# MCU_nRF5340.net
KiCad netlist of a schematic drawn in Altium Designer
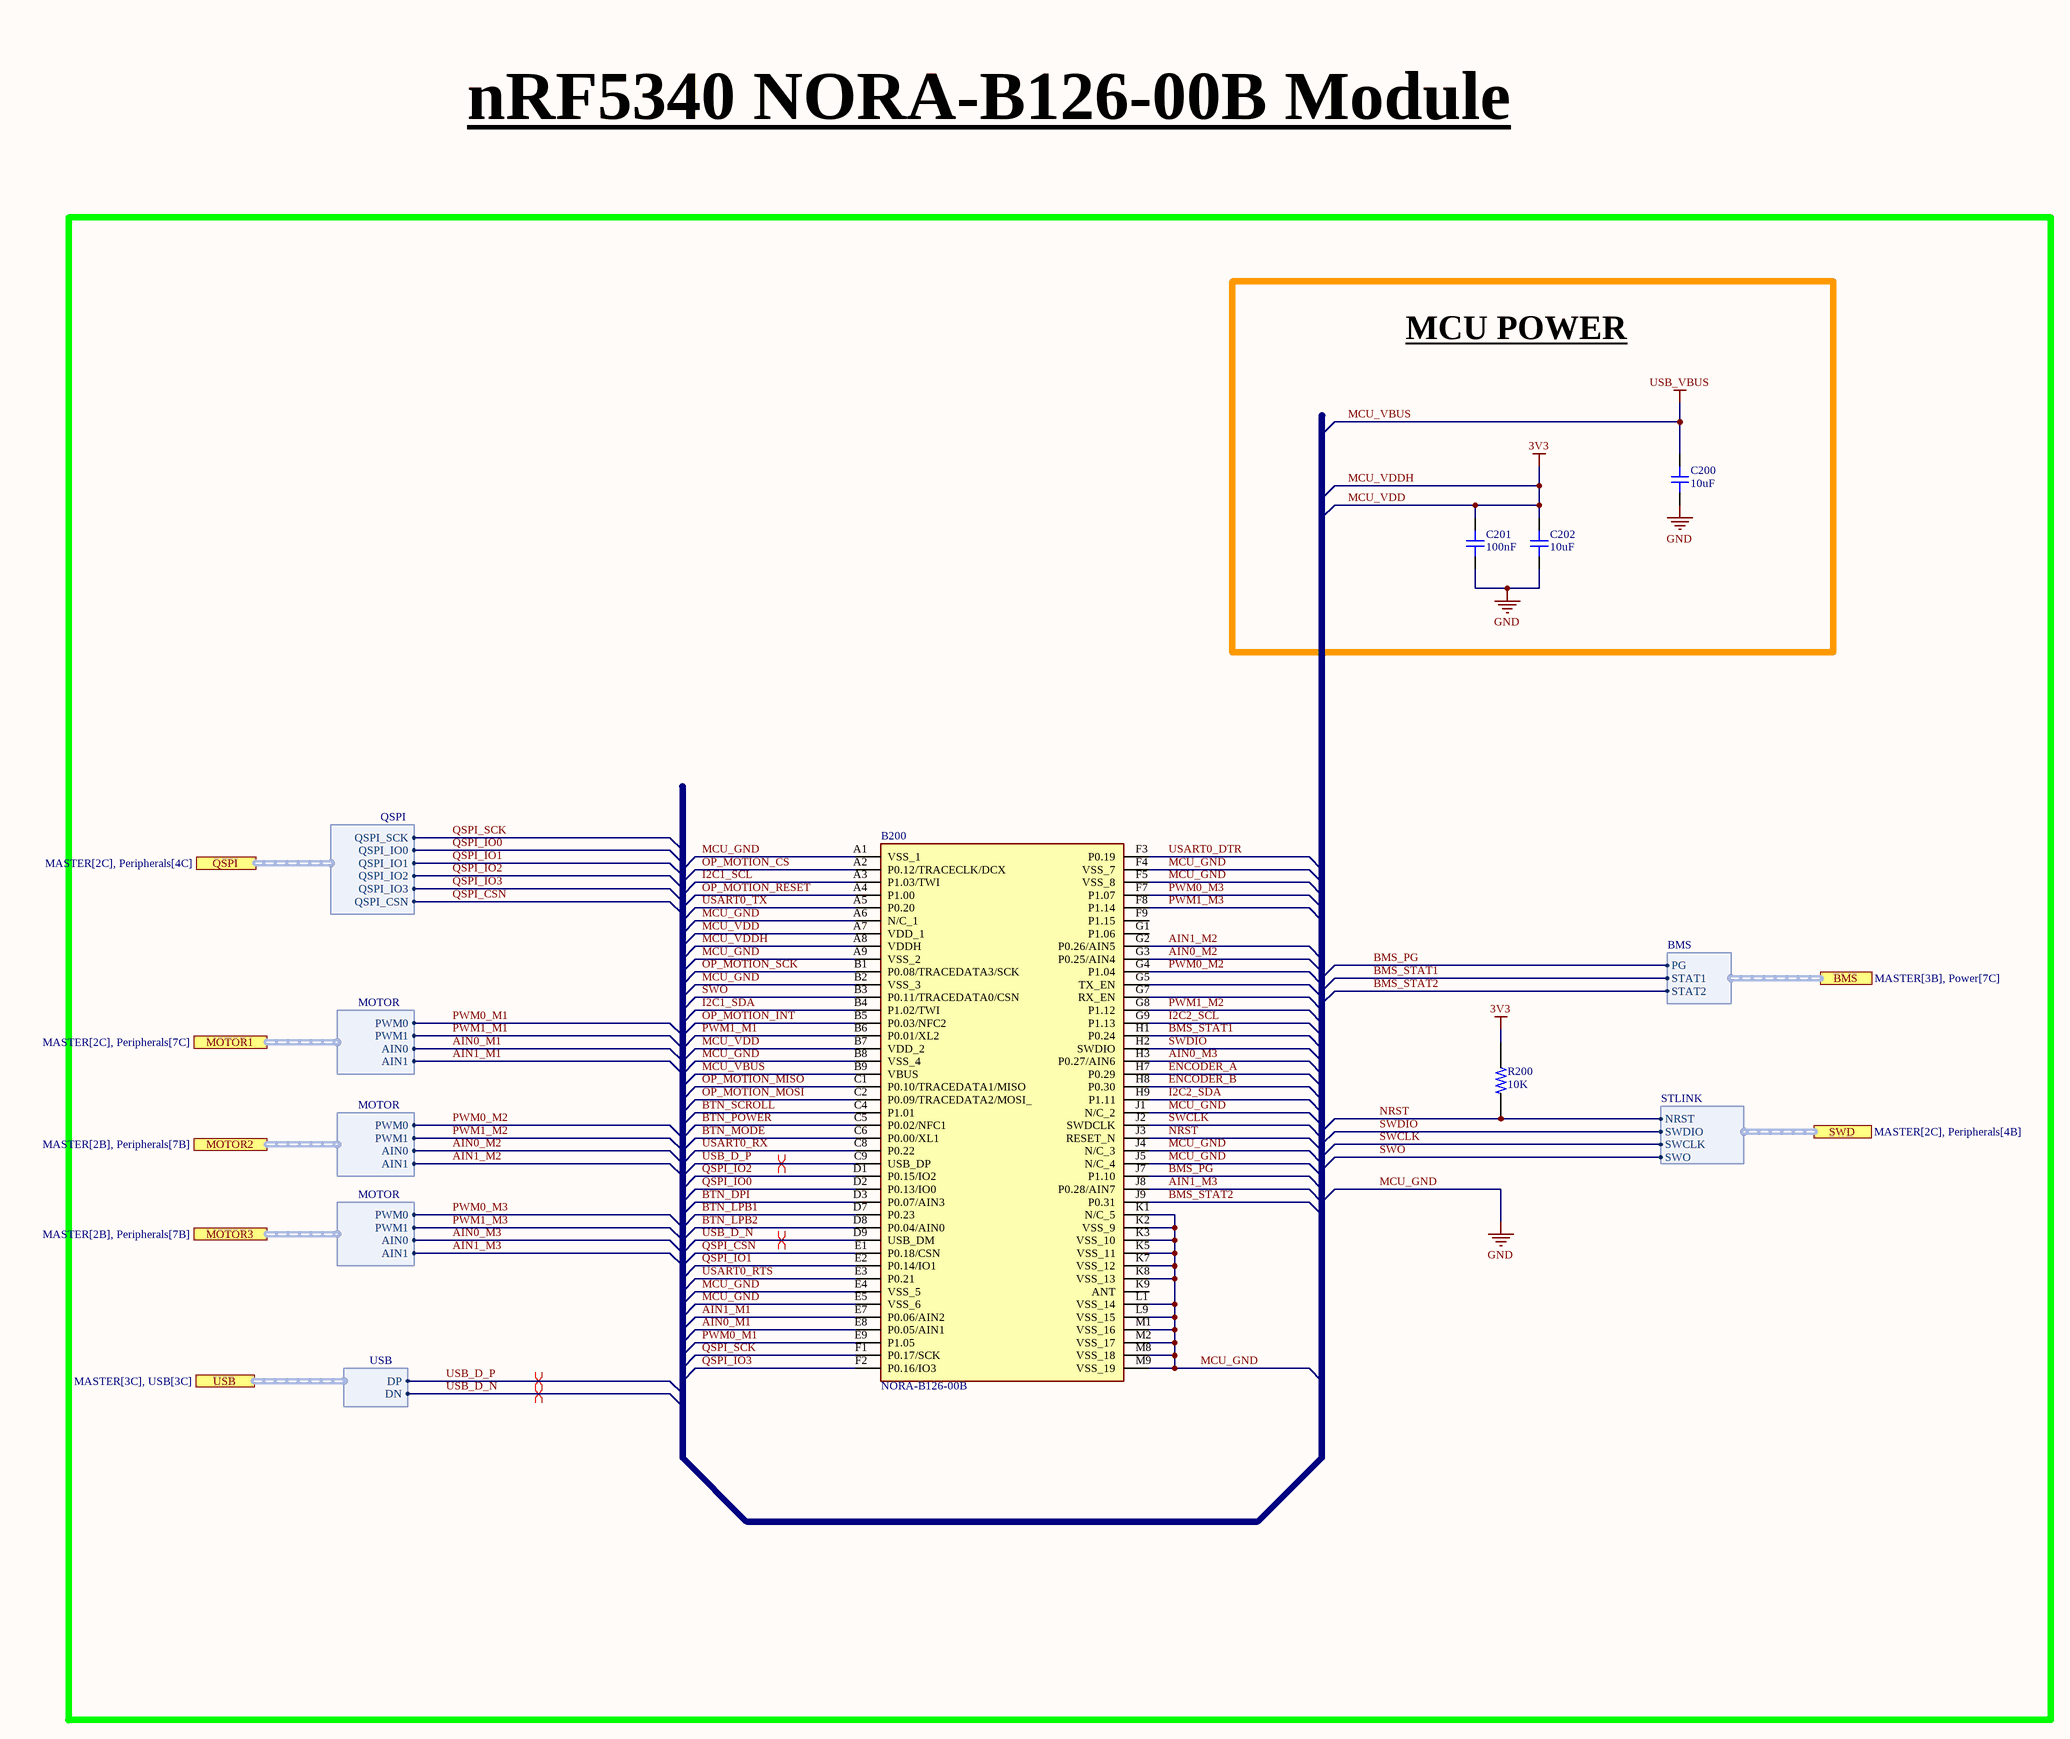
[diagram p0: MCU_nRF5340.SchDoc]

(export (version "E")
  (design (tool "Eeschema 10.0.6"))
  (components
    (comp (ref "B200")
      (value "NORA-B126-00B")
      (footprint "NORAB12600B")
      (description "Stand-alone dual-core Bluetooth 5.2 Low Energy and IEEE 802.15.4 module")
      (fields (field (name "MOUSER PART NUMBER") "377-NORA-B126-00B"))
      (libsource (lib "board") (part "NORA-B126-00B"))
    )
    (comp (ref "C200")
      (value "10uF")
      (footprint "CAP_0603")
      (description "Capacitor SMD 0603")
      (libsource (lib "board") (part "CAP_0603"))
    )
    (comp (ref "C201")
      (value "100nF")
      (footprint "CAP_0603")
      (description "Capacitor SMD 0603")
      (libsource (lib "board") (part "CAP_0603"))
    )
    (comp (ref "C202")
      (value "10uF")
      (footprint "CAP_0603")
      (description "Capacitor SMD 0603")
      (libsource (lib "board") (part "CAP_0603"))
    )
    (comp (ref "R200")
      (value "10K")
      (footprint "RESC1607X60N")
      (description "10 kOhms Â±5% 0.1W, 1/10W Chip Resistor 0603 (1608 Metric) Moisture Resistant Thick Film")
      (fields (field (name "MF") "Yageo") (field (name "MP") "RC0603JR0710KL"))
      (libsource (lib "board") (part "RC0603JR0710KL"))
    )
  )
  (nets
    (net (code "6") (name "/AIN0_M1") (class "Default")
      (node (ref "B200") (pin "E8") (pinfunction "P0.05/AIN1_E8") (pintype "passive"))
    )
    (net (code "7") (name "/AIN0_M2") (class "Default")
      (node (ref "B200") (pin "G3") (pinfunction "P0.25/AIN4_G3") (pintype "passive"))
    )
    (net (code "8") (name "/AIN0_M3") (class "Default")
      (node (ref "B200") (pin "H3") (pinfunction "P0.27/AIN6_H3") (pintype "passive"))
    )
    (net (code "9") (name "/AIN1_M1") (class "Default")
      (node (ref "B200") (pin "E7") (pinfunction "P0.06/AIN2_E7") (pintype "passive"))
    )
    (net (code "10") (name "/AIN1_M2") (class "Default")
      (node (ref "B200") (pin "G2") (pinfunction "P0.26/AIN5_G2") (pintype "passive"))
    )
    (net (code "11") (name "/AIN1_M3") (class "Default")
      (node (ref "B200") (pin "J8") (pinfunction "P0.28/AIN7_J8") (pintype "passive"))
    )
    (net (code "12") (name "/BMS_PG") (class "Default")
      (node (ref "B200") (pin "J7") (pinfunction "P1.10_J7") (pintype "passive"))
    )
    (net (code "13") (name "/BMS_STAT1") (class "Default")
      (node (ref "B200") (pin "H1") (pinfunction "P0.24_H1") (pintype "passive"))
    )
    (net (code "14") (name "/BMS_STAT2") (class "Default")
      (node (ref "B200") (pin "J9") (pinfunction "P0.31_J9") (pintype "passive"))
    )
    (net (code "15") (name "/BTN_DPI") (class "Default")
      (node (ref "B200") (pin "D3") (pinfunction "P0.07/AIN3_D3") (pintype "passive"))
    )
    (net (code "16") (name "/BTN_LPB1") (class "Default")
      (node (ref "B200") (pin "D7") (pinfunction "P0.23_D7") (pintype "passive"))
    )
    (net (code "17") (name "/BTN_LPB2") (class "Default")
      (node (ref "B200") (pin "D8") (pinfunction "P0.04/AIN0_D8") (pintype "passive"))
    )
    (net (code "18") (name "/BTN_MODE") (class "Default")
      (node (ref "B200") (pin "C6") (pinfunction "P0.00/XL1_C6") (pintype "passive"))
    )
    (net (code "19") (name "/BTN_POWER") (class "Default")
      (node (ref "B200") (pin "C5") (pinfunction "P0.02/NFC1_C5") (pintype "passive"))
    )
    (net (code "20") (name "/BTN_SCROLL") (class "Default")
      (node (ref "B200") (pin "C4") (pinfunction "P1.01_C4") (pintype "passive"))
    )
    (net (code "21") (name "/ENCODER_A") (class "Default")
      (node (ref "B200") (pin "H7") (pinfunction "P0.29_H7") (pintype "passive"))
    )
    (net (code "22") (name "/ENCODER_B") (class "Default")
      (node (ref "B200") (pin "H8") (pinfunction "P0.30_H8") (pintype "passive"))
    )
    (net (code "23") (name "/I2C1_SCL") (class "Default")
      (node (ref "B200") (pin "A3") (pinfunction "P1.03/TWI_A3") (pintype "passive"))
    )
    (net (code "24") (name "/I2C1_SDA") (class "Default")
      (node (ref "B200") (pin "B4") (pinfunction "P1.02/TWI_B4") (pintype "passive"))
    )
    (net (code "25") (name "/I2C2_SCL") (class "Default")
      (node (ref "B200") (pin "G9") (pinfunction "P1.13_G9") (pintype "passive"))
    )
    (net (code "26") (name "/I2C2_SDA") (class "Default")
      (node (ref "B200") (pin "H9") (pinfunction "P1.11_H9") (pintype "passive"))
    )
    (net (code "27") (name "/NRST") (class "Default")
      (node (ref "B200") (pin "J3") (pinfunction "RESET_N_J3") (pintype "passive"))
      (node (ref "R200") (pin "2") (pinfunction "2_2") (pintype "passive"))
    )
    (net (code "28") (name "/OP_MOTION_CS") (class "Default")
      (node (ref "B200") (pin "A2") (pinfunction "P0.12/TRACECLK/DCX_A2") (pintype "passive"))
    )
    (net (code "29") (name "/OP_MOTION_INT") (class "Default")
      (node (ref "B200") (pin "B5") (pinfunction "P0.03/NFC2_B5") (pintype "passive"))
    )
    (net (code "30") (name "/OP_MOTION_MISO") (class "Default")
      (node (ref "B200") (pin "C1") (pinfunction "P0.10/TRACEDATA1/MISO_C1") (pintype "passive"))
    )
    (net (code "31") (name "/OP_MOTION_MOSI") (class "Default")
      (node (ref "B200") (pin "C2") (pinfunction "P0.09/TRACEDATA2/MOSI__C2") (pintype "passive"))
    )
    (net (code "32") (name "/OP_MOTION_RESET") (class "Default")
      (node (ref "B200") (pin "A4") (pinfunction "P1.00_A4") (pintype "passive"))
    )
    (net (code "33") (name "/OP_MOTION_SCK") (class "Default")
      (node (ref "B200") (pin "B1") (pinfunction "P0.08/TRACEDATA3/SCK_B1") (pintype "passive"))
    )
    (net (code "34") (name "/PWM0_M1") (class "Default")
      (node (ref "B200") (pin "E9") (pinfunction "P1.05_E9") (pintype "passive"))
    )
    (net (code "35") (name "/PWM0_M2") (class "Default")
      (node (ref "B200") (pin "G4") (pinfunction "P1.04_G4") (pintype "passive"))
    )
    (net (code "36") (name "/PWM0_M3") (class "Default")
      (node (ref "B200") (pin "F7") (pinfunction "P1.07_F7") (pintype "passive"))
    )
    (net (code "37") (name "/PWM1_M1") (class "Default")
      (node (ref "B200") (pin "B6") (pinfunction "P0.01/XL2_B6") (pintype "passive"))
    )
    (net (code "38") (name "/PWM1_M2") (class "Default")
      (node (ref "B200") (pin "G8") (pinfunction "P1.12_G8") (pintype "passive"))
    )
    (net (code "39") (name "/PWM1_M3") (class "Default")
      (node (ref "B200") (pin "F8") (pinfunction "P1.14_F8") (pintype "passive"))
    )
    (net (code "40") (name "/QSPI_CSN") (class "Default")
      (node (ref "B200") (pin "E1") (pinfunction "P0.18/CSN_E1") (pintype "passive"))
    )
    (net (code "41") (name "/QSPI_IO0") (class "Default")
      (node (ref "B200") (pin "D2") (pinfunction "P0.13/IO0_D2") (pintype "passive"))
    )
    (net (code "42") (name "/QSPI_IO1") (class "Default")
      (node (ref "B200") (pin "E2") (pinfunction "P0.14/IO1_E2") (pintype "passive"))
    )
    (net (code "43") (name "/QSPI_IO2") (class "Default")
      (node (ref "B200") (pin "D1") (pinfunction "P0.15/IO2_D1") (pintype "passive"))
    )
    (net (code "44") (name "/QSPI_IO3") (class "Default")
      (node (ref "B200") (pin "F2") (pinfunction "P0.16/IO3_F2") (pintype "passive"))
    )
    (net (code "45") (name "/QSPI_SCK") (class "Default")
      (node (ref "B200") (pin "F1") (pinfunction "P0.17/SCK_F1") (pintype "passive"))
    )
    (net (code "46") (name "/SWCLK") (class "Default")
      (node (ref "B200") (pin "J2") (pinfunction "SWDCLK_J2") (pintype "passive"))
    )
    (net (code "47") (name "/SWDIO") (class "Default")
      (node (ref "B200") (pin "H2") (pinfunction "SWDIO_H2") (pintype "passive"))
    )
    (net (code "48") (name "/SWO") (class "Default")
      (node (ref "B200") (pin "B3") (pinfunction "P0.11/TRACEDATA0/CSN_B3") (pintype "passive"))
    )
    (net (code "49") (name "/USART0_DTR") (class "Default")
      (node (ref "B200") (pin "F3") (pinfunction "P0.19_F3") (pintype "passive"))
    )
    (net (code "50") (name "/USART0_RTS") (class "Default")
      (node (ref "B200") (pin "E3") (pinfunction "P0.21_E3") (pintype "passive"))
    )
    (net (code "51") (name "/USART0_RX") (class "Default")
      (node (ref "B200") (pin "C8") (pinfunction "P0.22_C8") (pintype "passive"))
    )
    (net (code "52") (name "/USART0_TX") (class "Default")
      (node (ref "B200") (pin "A5") (pinfunction "P0.20_A5") (pintype "passive"))
    )
    (net (code "53") (name "/USB_D_N") (class "Default")
      (node (ref "B200") (pin "D9") (pinfunction "USB_DM_D9") (pintype "passive"))
    )
    (net (code "54") (name "/USB_D_P") (class "Default")
      (node (ref "B200") (pin "C9") (pinfunction "USB_DP_C9") (pintype "passive"))
    )
    (net (code "60") (name "3V3") (class "Default")
      (node (ref "B200") (pin "A7") (pinfunction "VDD_1_A7") (pintype "passive"))
      (node (ref "B200") (pin "A8") (pinfunction "VDDH_A8") (pintype "passive"))
      (node (ref "B200") (pin "B7") (pinfunction "VDD_2_B7") (pintype "passive"))
      (node (ref "C201") (pin "2") (pinfunction "2_2") (pintype "passive"))
      (node (ref "C202") (pin "2") (pinfunction "2_2") (pintype "passive"))
      (node (ref "R200") (pin "1") (pinfunction "1_1") (pintype "passive"))
    )
    (net (code "61") (name "GND") (class "Default")
      (node (ref "B200") (pin "A1") (pinfunction "VSS_1_A1") (pintype "passive"))
      (node (ref "B200") (pin "A6") (pinfunction "N/C_1_A6") (pintype "passive"))
      (node (ref "B200") (pin "A9") (pinfunction "VSS_2_A9") (pintype "passive"))
      (node (ref "B200") (pin "B2") (pinfunction "VSS_3_B2") (pintype "passive"))
      (node (ref "B200") (pin "B8") (pinfunction "VSS_4_B8") (pintype "passive"))
      (node (ref "B200") (pin "E4") (pinfunction "VSS_5_E4") (pintype "passive"))
      (node (ref "B200") (pin "E5") (pinfunction "VSS_6_E5") (pintype "passive"))
      (node (ref "B200") (pin "F4") (pinfunction "VSS_7_F4") (pintype "passive"))
      (node (ref "B200") (pin "F5") (pinfunction "VSS_8_F5") (pintype "passive"))
      (node (ref "B200") (pin "J1") (pinfunction "N/C_2_J1") (pintype "passive"))
      (node (ref "B200") (pin "J4") (pinfunction "N/C_3_J4") (pintype "passive"))
      (node (ref "B200") (pin "J5") (pinfunction "N/C_4_J5") (pintype "passive"))
      (node (ref "B200") (pin "K1") (pinfunction "N/C_5_K1") (pintype "passive"))
      (node (ref "B200") (pin "K2") (pinfunction "VSS_9_K2") (pintype "passive"))
      (node (ref "B200") (pin "K3") (pinfunction "VSS_10_K3") (pintype "passive"))
      (node (ref "B200") (pin "K5") (pinfunction "VSS_11_K5") (pintype "passive"))
      (node (ref "B200") (pin "K7") (pinfunction "VSS_12_K7") (pintype "passive"))
      (node (ref "B200") (pin "K8") (pinfunction "VSS_13_K8") (pintype "passive"))
      (node (ref "B200") (pin "L1") (pinfunction "VSS_14_L1") (pintype "passive"))
      (node (ref "B200") (pin "L9") (pinfunction "VSS_15_L9") (pintype "passive"))
      (node (ref "B200") (pin "M1") (pinfunction "VSS_16_M1") (pintype "passive"))
      (node (ref "B200") (pin "M2") (pinfunction "VSS_17_M2") (pintype "passive"))
      (node (ref "B200") (pin "M8") (pinfunction "VSS_18_M8") (pintype "passive"))
      (node (ref "B200") (pin "M9") (pinfunction "VSS_19_M9") (pintype "passive"))
      (node (ref "C200") (pin "1") (pinfunction "1_1") (pintype "passive"))
      (node (ref "C201") (pin "1") (pinfunction "1_1") (pintype "passive"))
      (node (ref "C202") (pin "1") (pinfunction "1_1") (pintype "passive"))
    )
    (net (code "62") (name "USB_VBUS") (class "Default")
      (node (ref "B200") (pin "B9") (pinfunction "VBUS_B9") (pintype "passive"))
      (node (ref "C200") (pin "2") (pinfunction "2_2") (pintype "passive"))
    )
    (net (code "63") (name "unconnected-(B200-ANT-PadK9)") (class "Default")
      (node (ref "B200") (pin "K9") (pinfunction "ANT_K9") (pintype "passive"))
    )
    (net (code "64") (name "unconnected-(B200-P1.06-PadG1)") (class "Default")
      (node (ref "B200") (pin "G1") (pinfunction "P1.06_G1") (pintype "passive"))
    )
    (net (code "65") (name "unconnected-(B200-P1.15-PadF9)") (class "Default")
      (node (ref "B200") (pin "F9") (pinfunction "P1.15_F9") (pintype "passive"))
    )
    (net (code "66") (name "unconnected-(B200-RX_EN-PadG7)") (class "Default")
      (node (ref "B200") (pin "G7") (pinfunction "RX_EN_G7") (pintype "passive"))
    )
    (net (code "67") (name "unconnected-(B200-TX_EN-PadG5)") (class "Default")
      (node (ref "B200") (pin "G5") (pinfunction "TX_EN_G5") (pintype "passive"))
    )
  )
)
